# led555.net
KiCad netlist of a schematic drawn in EAGLE
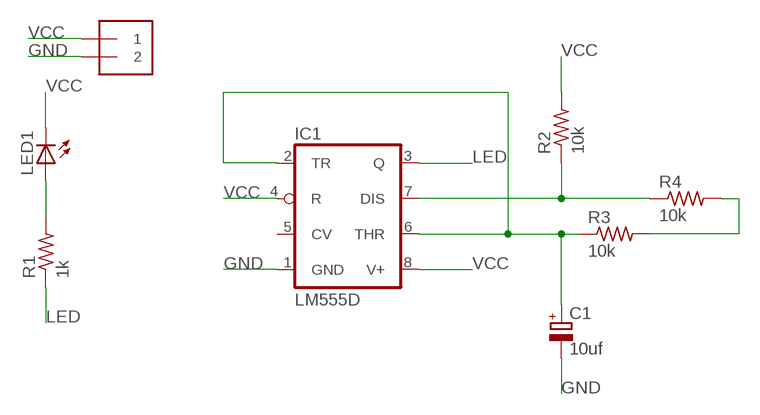
[diagram p0: schematic, sheet 1]

(export (version "E")
  (design (tool "Eeschema 10.0.6"))
  (components
    (comp (ref "C1")
      (value "10uf")
      (footprint "eagle-import:140CLH-0810")
      (libsource (lib "eagle-import") (part "CPOL-EU140CLH-0810"))
    )
    (comp (ref "IC1")
      (value "LM555D")
      (footprint "eagle-import:SO08")
      (libsource (lib "eagle-import") (part "555DLM"))
    )
    (comp (ref "J1")
      (value "power")
      (footprint "eagle-import:1X2-3.5MM")
      (libsource (lib "eagle-import") (part "1X2-3.5MM"))
    )
    (comp (ref "LED1")
      (value "LED5MM")
      (footprint "eagle-import:LED5MM")
      (libsource (lib "eagle-import") (part "LED5MM"))
    )
    (comp (ref "R1")
      (value "1k")
      (footprint "eagle-import:M1206")
      (libsource (lib "eagle-import") (part "R-US_M1206"))
    )
    (comp (ref "R2")
      (value "10k")
      (footprint "eagle-import:M1206")
      (libsource (lib "eagle-import") (part "R-US_M1206"))
    )
    (comp (ref "R3")
      (value "10k")
      (footprint "eagle-import:M1206")
      (libsource (lib "eagle-import") (part "R-US_M1206"))
    )
    (comp (ref "R4")
      (value "10k")
      (footprint "eagle-import:M1206")
      (libsource (lib "eagle-import") (part "R-US_M1206"))
    )
  )
  (nets
    (net (code "1") (name "/GND") (class "Default")
      (node (ref "C1") (pin "-") (pinfunction "-_-") (pintype "passive"))
      (node (ref "IC1") (pin "1") (pinfunction "GND_1") (pintype "power_in"))
      (node (ref "J1") (pin "2") (pinfunction "2_2") (pintype "passive"))
    )
    (net (code "2") (name "/LED") (class "Default")
      (node (ref "IC1") (pin "3") (pinfunction "Q_3") (pintype "output"))
      (node (ref "R1") (pin "1") (pinfunction "1_1") (pintype "passive"))
    )
    (net (code "3") (name "/VCC") (class "Default")
      (node (ref "IC1") (pin "4") (pinfunction "R_4") (pintype "input"))
      (node (ref "IC1") (pin "8") (pinfunction "V+_8") (pintype "power_in"))
      (node (ref "J1") (pin "1") (pinfunction "1_1") (pintype "passive"))
      (node (ref "LED1") (pin "K") (pinfunction "C_K") (pintype "passive"))
      (node (ref "R2") (pin "2") (pinfunction "2_2") (pintype "passive"))
    )
    (net (code "4") (name "Net-(IC1-DIS)") (class "Default")
      (node (ref "IC1") (pin "7") (pinfunction "DIS_7") (pintype "input"))
      (node (ref "R2") (pin "1") (pinfunction "1_1") (pintype "passive"))
      (node (ref "R4") (pin "1") (pinfunction "1_1") (pintype "passive"))
    )
    (net (code "5") (name "Net-(IC1-THR)") (class "Default")
      (node (ref "C1") (pin "+") (pinfunction "+_+") (pintype "passive"))
      (node (ref "IC1") (pin "2") (pinfunction "TR_2") (pintype "input"))
      (node (ref "IC1") (pin "6") (pinfunction "THR_6") (pintype "input"))
      (node (ref "R3") (pin "1") (pinfunction "1_1") (pintype "passive"))
    )
    (net (code "6") (name "Net-(LED1-PadA)") (class "Default")
      (node (ref "LED1") (pin "A") (pinfunction "A_A") (pintype "passive"))
      (node (ref "R1") (pin "2") (pinfunction "2_2") (pintype "passive"))
    )
    (net (code "7") (name "Net-(R3-Pad2)") (class "Default")
      (node (ref "R3") (pin "2") (pinfunction "2_2") (pintype "passive"))
      (node (ref "R4") (pin "2") (pinfunction "2_2") (pintype "passive"))
    )
    (net (code "8") (name "unconnected-(IC1-CV-Pad5)") (class "Default")
      (node (ref "IC1") (pin "5") (pinfunction "CV_5") (pintype "input"))
    )
  )
)
